# Encoder.net
KiCad netlist of a schematic drawn in Altium Designer
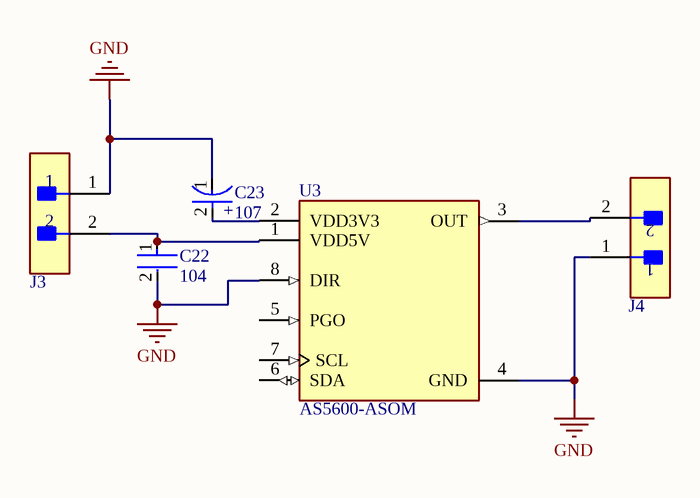
[diagram p0: Encoder.SchDoc]

(export (version "E")
  (design (tool "Eeschema 10.0.6"))
  (components
    (comp (ref "C22")
      (value "104")
      (footprint "FP-CC0603-DA-MFG")
      (description "CAP CER 0.1UF 16V X7R 0603")
      (fields
        (field (name "OCTOPART") "https://octopart.com/cc0603krx7r7bb104-yageo-192941")
        (field (name "TOLERANCE") "0.1")
      )
      (libsource (lib "Altium Content Vault") (part "11868f565c42a9108669ba33697ecf6"))
    )
    (comp (ref "C23")
      (value "107")
      (footprint "FP-T491B105K035AT-MFG")
      (description "CAP TANT 1UF 10% 35V 1411")
      (fields (field (name "VOLTAGE") "35V") (field (name "TOLERANCE") "20%"))
      (libsource (lib "Altium Content Vault") (part "203bc49f2ac43e59fd269a8c329ed05"))
    )
    (comp (ref "J3")
      (value "M20-9990246")
      (footprint "FP-M20-9990246-MFG")
      (description "Connector Header Through Hole 2 position 0.100\" (2.54mm)")
      (fields (field (name "OCTOPART") "https://octopart.com/m20-9990246-harwin-2590635"))
      (libsource (lib "Altium Content Vault") (part "3bc925449376181038e59eaffc5286c"))
    )
    (comp (ref "J4")
      (value "M20-9990246")
      (footprint "FP-M20-9990246-MFG")
      (description "Connector Header Through Hole 2 position 0.100\" (2.54mm)")
      (fields (field (name "OCTOPART") "https://octopart.com/m20-9990246-harwin-2590635"))
      (libsource (lib "") (part "3bc925449376181038e59eaffc5286c_1"))
    )
    (comp (ref "U3")
      (value "AS5600-ASOM")
      (footprint "FP-AS5600-ASOM-IPC_C")
      (description "SENSOR ANGLE 360DEG SMD")
      (libsource (lib "Altium Content Vault") (part "7a1e9824f8ff8a913d90a1366781b5b"))
    )
  )
  (nets
    (net (code "1") (name "GND") (class "Default")
      (node (ref "C22") (pin "2") (pinfunction "2_2") (pintype "passive"))
      (node (ref "C23") (pin "1") (pinfunction "C_1") (pintype "passive"))
      (node (ref "J3") (pin "1") (pinfunction "1_1") (pintype "passive"))
      (node (ref "J4") (pin "1") (pinfunction "1_1") (pintype "passive"))
      (node (ref "U3") (pin "4") (pinfunction "GND_4") (pintype "power_in"))
      (node (ref "U3") (pin "8") (pinfunction "DIR_8") (pintype "input"))
    )
    (net (code "2") (name "Net-(C23-A)") (class "Default")
      (node (ref "C23") (pin "2") (pinfunction "A_2") (pintype "passive"))
      (node (ref "U3") (pin "2") (pinfunction "VDD3V3_2") (pintype "power_in"))
    )
    (net (code "3") (name "Net-(U3-OUT)") (class "Default")
      (node (ref "J4") (pin "2") (pinfunction "2_2") (pintype "passive"))
      (node (ref "U3") (pin "3") (pinfunction "OUT_3") (pintype "output"))
    )
    (net (code "4") (name "Net-(U3-VDD5V)") (class "Default")
      (node (ref "C22") (pin "1") (pinfunction "1_1") (pintype "passive"))
      (node (ref "J3") (pin "2") (pinfunction "2_2") (pintype "passive"))
      (node (ref "U3") (pin "1") (pinfunction "VDD5V_1") (pintype "power_in"))
    )
    (net (code "5") (name "unconnected-(U3-PGO-Pad5)") (class "Default")
      (node (ref "U3") (pin "5") (pinfunction "PGO_5") (pintype "input"))
    )
    (net (code "6") (name "unconnected-(U3-SCL-Pad7)") (class "Default")
      (node (ref "U3") (pin "7") (pinfunction "SCL_7") (pintype "input"))
    )
    (net (code "7") (name "unconnected-(U3-SDA-Pad6)") (class "Default")
      (node (ref "U3") (pin "6") (pinfunction "SDA_6") (pintype "bidirectional"))
    )
  )
)
